# 1_Interface.net
KiCad netlist of a schematic drawn in Altium Designer
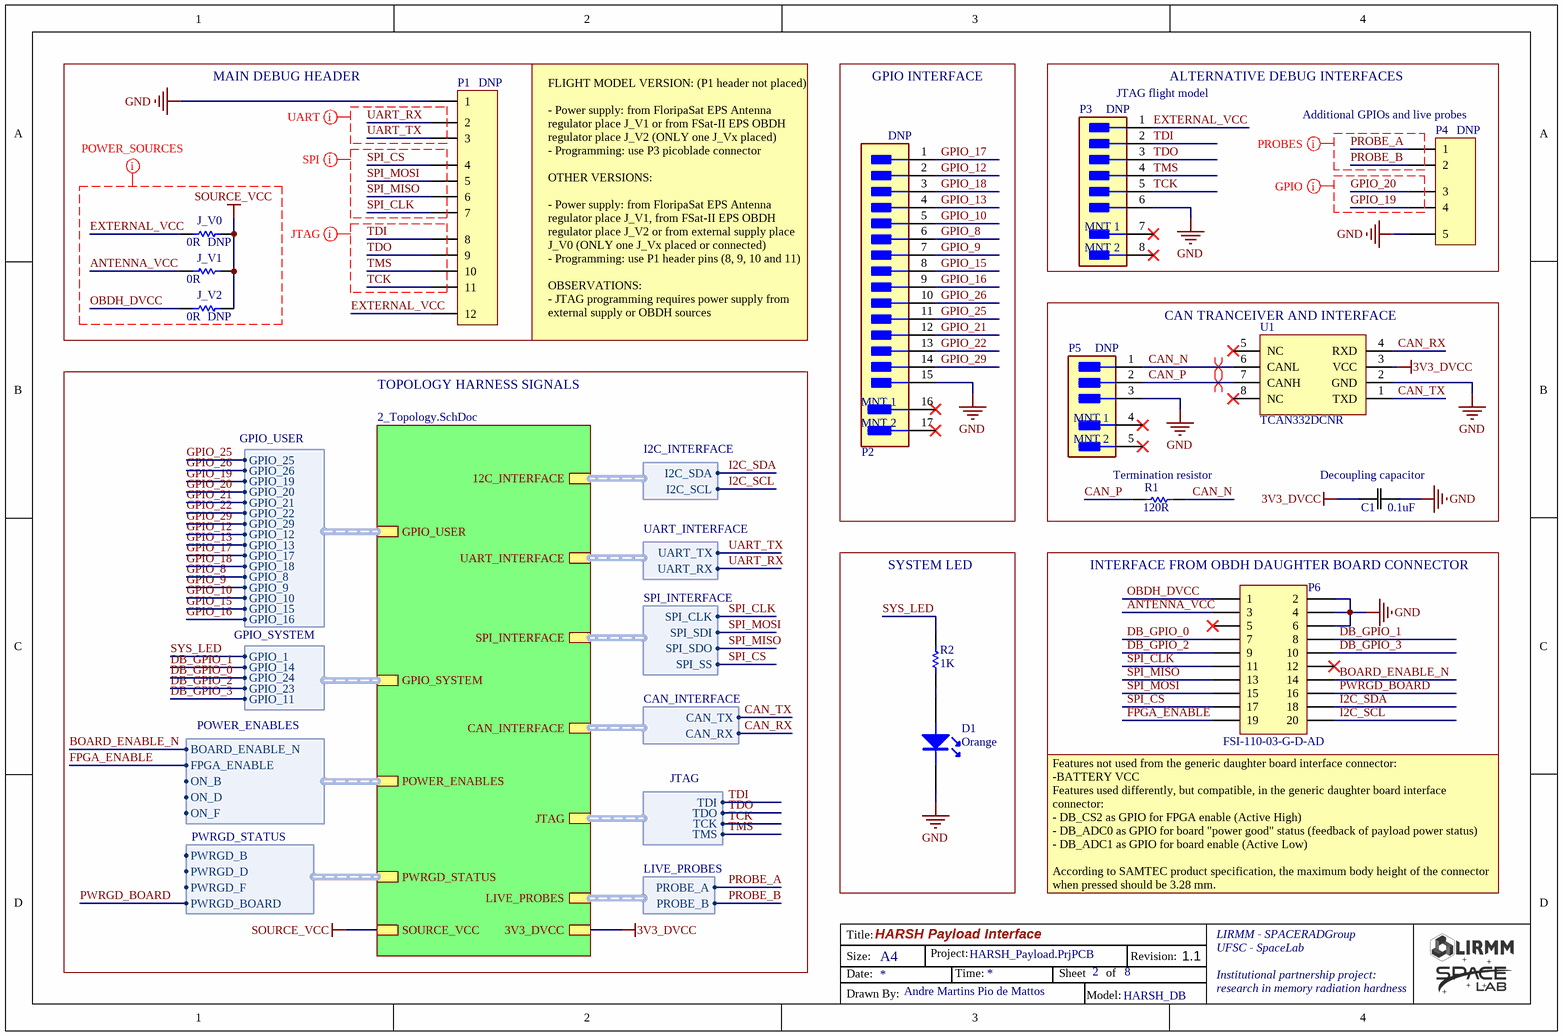
[diagram p0: 1_Interface.SchDoc]

(export (version "E")
  (design (tool "Eeschema 10.0.6"))
  (components
    (comp (ref "C1")
      (value "100nF/50V")
      (footprint "DONE_C0603")
      (description "CAP CER 100nF 50V 0603 10%")
      (fields
        (field (name "PARTNUMBER") "C0603C104K5RAC3121")
        (field (name "MANUFACTURER") "Yageo")
        (field (name "CAPACITANCE") "0.1uF")
      )
      (libsource (lib "HARSH_Payload_SchLib") (part "DONE_CAP_0.1uF_0603_X7R"))
    )
    (comp (ref "D1")
      (value "Orange")
      (footprint "DONE_D0603_ORANGE")
      (description "SMD Orange LED")
      (fields (field (name "PARTNUMBER") "HSML-C191-T0000"))
      (libsource (lib "HARSH_Payload_SchLib") (part "DONE_LED_ORANGE_0603"))
    )
    (comp (ref "J_V0")
      (value "0R")
      (footprint "DONE_R0603")
      (description "RES SMD 0 OHM JUMPER 1/10W 0603")
      (fields (field (name "PARTNUMBER") "RC0603JR-070RL"))
      (libsource (lib "HARSH_Payload_SchLib") (part "DONE_RES_0R_0603"))
    )
    (comp (ref "J_V1")
      (value "0R")
      (footprint "DONE_R0603")
      (description "RES SMD 0 OHM JUMPER 1/10W 0603")
      (fields (field (name "PARTNUMBER") "RC0603JR-070RL"))
      (libsource (lib "HARSH_Payload_SchLib") (part "DONE_RES_0R_0603"))
    )
    (comp (ref "J_V2")
      (value "0R")
      (footprint "DONE_R0603")
      (description "RES SMD 0 OHM JUMPER 1/10W 0603")
      (fields (field (name "PARTNUMBER") "RC0603JR-070RL"))
      (libsource (lib "HARSH_Payload_SchLib") (part "DONE_RES_0R_0603"))
    )
    (comp (ref "P1")
      (value "Header 12H")
      (footprint "DONE_H1X12_PADS")
      (description "Header, 12-Pin")
      (fields (field (name "PUBLISHER") "Altium Limited"))
      (libsource (lib "HARSH_Payload_SchLib") (part "DONE_H1X12_PADS"))
    )
    (comp (ref "P2")
      (value "53261-1571")
      (footprint "DONE_PICOBLADE_15H_HORIZONTAL")
      (description "Picoblade, 15 pos, Right-angle, 53261-1571")
      (libsource (lib "HARSH_Payload_SchLib") (part "DONE_PICOBLADE_15H"))
    )
    (comp (ref "P3")
      (value "53261-0671")
      (footprint "DONE_PICOBLADE_6H_HORIZONTAL")
      (description "Picoblade, 6 pos, Right-angle")
      (libsource (lib "HARSH_Payload_SchLib") (part "DONE_PICOBLADE_6H"))
    )
    (comp (ref "P4")
      (value "Header 5H")
      (footprint "DONE_H1X5_PADS")
      (description "Header, 5-Pin, Pads")
      (fields (field (name "PUBLISHER") "Altium Limited"))
      (libsource (lib "HARSH_Payload_SchLib") (part "DONE_H1X5_PADS"))
    )
    (comp (ref "P5")
      (value "53261-0371")
      (footprint "DONE_PICOBLADE_3H_HORIZONTAL")
      (description "Picoblade, 3 pos, Right-angle")
      (libsource (lib "HARSH_Payload_SchLib") (part "DONE_PICOBLADE_3H"))
    )
    (comp (ref "P6")
      (value "FSI-110-03-G-D-AD")
      (footprint "DONE_DB_INTERFACE")
      (description "CONN STACKING 20POS SMD GOLD")
      (fields
        (field (name "MANUFACTURER") "Samtec")
        (field (name "MANUFACTURER PART NUMBER") "FSI-110-03-G-D-AD")
      )
      (libsource (lib "HARSH_Payload_SchLib") (part "DONE_DB_INTERFACE"))
    )
    (comp (ref "R1")
      (value "120R")
      (footprint "DONE_R0603")
      (description "120R 1% 0603")
      (fields (field (name "RESISTANCE") "120R") (field (name "PARTNUMBER") "RC0603FR-07120RL"))
      (libsource (lib "HARSH_Payload_SchLib") (part "DONE_RES_120R_0603"))
    )
    (comp (ref "R2")
      (value "1K")
      (footprint "DONE_R0603")
      (description "RES SMD 1K OHM 1% 1/4W 0603")
      (fields
        (field (name "MANUFACTURER") "Rohm")
        (field (name "MANUFACTURER PART NUMBER") "ESR03EZPF1001")
        (field (name "RESISTANCE") "1K")
      )
      (libsource (lib "HARSH_Payload_SchLib") (part "DONE_RES_1K_0603"))
    )
    (comp (ref "U1")
      (value "TCAN332DCNR")
      (footprint "DONE_TSOT_23_8")
      (description "Tranceiver CAN, 8-pin SOT23")
      (fields (field (name "MANUFACTURER") "Texas Instruments") (field (name "PARTNUMBER") "TCAN332DCNR"))
      (libsource (lib "HARSH_Payload_SchLib") (part "DONE_TCAN332DCNR"))
    )
  )
  (nets
    (net (code "11") (name "/ANTENNA_VCC") (class "Default")
      (node (ref "J_V1") (pin "2") (pinfunction "2_2") (pintype "passive"))
      (node (ref "P6") (pin "3") (pinfunction "3_3") (pintype "passive"))
    )
    (net (code "12") (name "/BOARD_ENABLE_N") (class "Default")
      (node (ref "P6") (pin "14") (pinfunction "14_14") (pintype "passive"))
    )
    (net (code "13") (name "/CAN_N") (class "Default")
      (node (ref "P5") (pin "1") (pinfunction "1_1") (pintype "passive"))
      (node (ref "R1") (pin "1") (pinfunction "1_1") (pintype "passive"))
      (node (ref "U1") (pin "6") (pinfunction "CANL_6") (pintype "passive"))
    )
    (net (code "14") (name "/CAN_P") (class "Default")
      (node (ref "P5") (pin "2") (pinfunction "2_2") (pintype "passive"))
      (node (ref "R1") (pin "2") (pinfunction "2_2") (pintype "passive"))
      (node (ref "U1") (pin "7") (pinfunction "CANH_7") (pintype "passive"))
    )
    (net (code "15") (name "/CAN_RX") (class "Default")
      (node (ref "U1") (pin "4") (pinfunction "RXD_4") (pintype "passive"))
    )
    (net (code "16") (name "/CAN_TX") (class "Default")
      (node (ref "U1") (pin "1") (pinfunction "TXD_1") (pintype "passive"))
    )
    (net (code "17") (name "/DB_GPIO_0") (class "Default")
      (node (ref "P6") (pin "7") (pinfunction "7_7") (pintype "passive"))
    )
    (net (code "18") (name "/DB_GPIO_1") (class "Default")
      (node (ref "P6") (pin "8") (pinfunction "8_8") (pintype "passive"))
    )
    (net (code "19") (name "/DB_GPIO_2") (class "Default")
      (node (ref "P6") (pin "9") (pinfunction "9_9") (pintype "passive"))
    )
    (net (code "20") (name "/DB_GPIO_3") (class "Default")
      (node (ref "P6") (pin "10") (pinfunction "10_10") (pintype "passive"))
    )
    (net (code "21") (name "/EXTERNAL_VCC") (class "Default")
      (node (ref "J_V0") (pin "2") (pinfunction "2_2") (pintype "passive"))
      (node (ref "P1") (pin "12") (pinfunction "12_12") (pintype "passive"))
      (node (ref "P3") (pin "1") (pinfunction "1_1") (pintype "passive"))
    )
    (net (code "22") (name "/FPGA_ENABLE") (class "Default")
      (node (ref "P6") (pin "19") (pinfunction "19_19") (pintype "passive"))
    )
    (net (code "23") (name "/GPIO_8") (class "Default")
      (node (ref "P2") (pin "6") (pinfunction "6_6") (pintype "passive"))
    )
    (net (code "24") (name "/GPIO_9") (class "Default")
      (node (ref "P2") (pin "7") (pinfunction "7_7") (pintype "passive"))
    )
    (net (code "25") (name "/GPIO_10") (class "Default")
      (node (ref "P2") (pin "5") (pinfunction "5_5") (pintype "passive"))
    )
    (net (code "26") (name "/GPIO_12") (class "Default")
      (node (ref "P2") (pin "2") (pinfunction "2_2") (pintype "passive"))
    )
    (net (code "27") (name "/GPIO_13") (class "Default")
      (node (ref "P2") (pin "4") (pinfunction "4_4") (pintype "passive"))
    )
    (net (code "28") (name "/GPIO_15") (class "Default")
      (node (ref "P2") (pin "8") (pinfunction "8_8") (pintype "passive"))
    )
    (net (code "29") (name "/GPIO_16") (class "Default")
      (node (ref "P2") (pin "9") (pinfunction "9_9") (pintype "passive"))
    )
    (net (code "30") (name "/GPIO_17") (class "Default")
      (node (ref "P2") (pin "1") (pinfunction "1_1") (pintype "passive"))
    )
    (net (code "31") (name "/GPIO_18") (class "Default")
      (node (ref "P2") (pin "3") (pinfunction "3_3") (pintype "passive"))
    )
    (net (code "32") (name "/GPIO_19") (class "Default")
      (node (ref "P4") (pin "4") (pinfunction "4_4") (pintype "passive"))
    )
    (net (code "33") (name "/GPIO_20") (class "Default")
      (node (ref "P4") (pin "3") (pinfunction "3_3") (pintype "passive"))
    )
    (net (code "34") (name "/GPIO_21") (class "Default")
      (node (ref "P2") (pin "12") (pinfunction "12_12") (pintype "passive"))
    )
    (net (code "35") (name "/GPIO_22") (class "Default")
      (node (ref "P2") (pin "13") (pinfunction "13_13") (pintype "passive"))
    )
    (net (code "36") (name "/GPIO_25") (class "Default")
      (node (ref "P2") (pin "11") (pinfunction "11_11") (pintype "passive"))
    )
    (net (code "37") (name "/GPIO_26") (class "Default")
      (node (ref "P2") (pin "10") (pinfunction "10_10") (pintype "passive"))
    )
    (net (code "38") (name "/GPIO_29") (class "Default")
      (node (ref "P2") (pin "14") (pinfunction "14_14") (pintype "passive"))
    )
    (net (code "39") (name "/I2C_SCL") (class "Default")
      (node (ref "P6") (pin "20") (pinfunction "20_20") (pintype "passive"))
    )
    (net (code "40") (name "/I2C_SDA") (class "Default")
      (node (ref "P6") (pin "18") (pinfunction "18_18") (pintype "passive"))
    )
    (net (code "41") (name "/OBDH_DVCC") (class "Default")
      (node (ref "J_V2") (pin "2") (pinfunction "2_2") (pintype "passive"))
      (node (ref "P6") (pin "1") (pinfunction "1_1") (pintype "passive"))
    )
    (net (code "42") (name "/PROBE_A") (class "Default")
      (node (ref "P4") (pin "1") (pinfunction "1_1") (pintype "passive"))
    )
    (net (code "43") (name "/PROBE_B") (class "Default")
      (node (ref "P4") (pin "2") (pinfunction "2_2") (pintype "passive"))
    )
    (net (code "44") (name "/PWRGD_BOARD") (class "Default")
      (node (ref "P6") (pin "16") (pinfunction "16_16") (pintype "passive"))
    )
    (net (code "45") (name "/SPI_CLK") (class "Default")
      (node (ref "P1") (pin "7") (pinfunction "7_7") (pintype "passive"))
      (node (ref "P6") (pin "11") (pinfunction "11_11") (pintype "passive"))
    )
    (net (code "46") (name "/SPI_CS") (class "Default")
      (node (ref "P1") (pin "4") (pinfunction "4_4") (pintype "passive"))
      (node (ref "P6") (pin "17") (pinfunction "17_17") (pintype "passive"))
    )
    (net (code "47") (name "/SPI_MISO") (class "Default")
      (node (ref "P1") (pin "6") (pinfunction "6_6") (pintype "passive"))
      (node (ref "P6") (pin "13") (pinfunction "13_13") (pintype "passive"))
    )
    (net (code "48") (name "/SPI_MOSI") (class "Default")
      (node (ref "P1") (pin "5") (pinfunction "5_5") (pintype "passive"))
      (node (ref "P6") (pin "15") (pinfunction "15_15") (pintype "passive"))
    )
    (net (code "49") (name "/SYS_LED") (class "Default")
      (node (ref "R2") (pin "2") (pinfunction "2_2") (pintype "passive"))
    )
    (net (code "50") (name "/TCK") (class "Default")
      (node (ref "P1") (pin "11") (pinfunction "11_11") (pintype "passive"))
      (node (ref "P3") (pin "5") (pinfunction "5_5") (pintype "passive"))
    )
    (net (code "51") (name "/TDI") (class "Default")
      (node (ref "P1") (pin "8") (pinfunction "8_8") (pintype "passive"))
      (node (ref "P3") (pin "2") (pinfunction "2_2") (pintype "passive"))
    )
    (net (code "52") (name "/TDO") (class "Default")
      (node (ref "P1") (pin "9") (pinfunction "9_9") (pintype "passive"))
      (node (ref "P3") (pin "3") (pinfunction "3_3") (pintype "passive"))
    )
    (net (code "53") (name "/TMS") (class "Default")
      (node (ref "P1") (pin "10") (pinfunction "10_10") (pintype "passive"))
      (node (ref "P3") (pin "4") (pinfunction "4_4") (pintype "passive"))
    )
    (net (code "54") (name "/UART_RX") (class "Default")
      (node (ref "P1") (pin "2") (pinfunction "2_2") (pintype "passive"))
    )
    (net (code "55") (name "/UART_TX") (class "Default")
      (node (ref "P1") (pin "3") (pinfunction "3_3") (pintype "passive"))
    )
    (net (code "66") (name "3V3_DVCC") (class "Default")
      (node (ref "C1") (pin "1") (pinfunction "1_1") (pintype "passive"))
      (node (ref "U1") (pin "3") (pinfunction "VCC_3") (pintype "passive"))
    )
    (net (code "67") (name "GND") (class "Default")
      (node (ref "C1") (pin "2") (pinfunction "2_2") (pintype "passive"))
      (node (ref "D1") (pin "2") (pinfunction "K_2") (pintype "passive"))
      (node (ref "P1") (pin "1") (pinfunction "1_1") (pintype "passive"))
      (node (ref "P2") (pin "15") (pinfunction "15_15") (pintype "passive"))
      (node (ref "P3") (pin "6") (pinfunction "6_6") (pintype "passive"))
      (node (ref "P4") (pin "5") (pinfunction "5_5") (pintype "passive"))
      (node (ref "P5") (pin "3") (pinfunction "3_3") (pintype "passive"))
      (node (ref "P6") (pin "2") (pinfunction "2_2") (pintype "passive"))
      (node (ref "P6") (pin "4") (pinfunction "4_4") (pintype "passive"))
      (node (ref "P6") (pin "6") (pinfunction "6_6") (pintype "passive"))
      (node (ref "U1") (pin "2") (pinfunction "GND_2") (pintype "passive"))
    )
    (net (code "68") (name "Net-(D1-A)") (class "Default")
      (node (ref "D1") (pin "1") (pinfunction "A_1") (pintype "passive"))
      (node (ref "R2") (pin "1") (pinfunction "1_1") (pintype "passive"))
    )
    (net (code "69") (name "SOURCE_VCC") (class "Default")
      (node (ref "J_V0") (pin "1") (pinfunction "1_1") (pintype "passive"))
      (node (ref "J_V1") (pin "1") (pinfunction "1_1") (pintype "passive"))
      (node (ref "J_V2") (pin "1") (pinfunction "1_1") (pintype "passive"))
    )
    (net (code "70") (name "unconnected-(P2-MNT_1-Pad16)") (class "Default")
      (node (ref "P2") (pin "16") (pinfunction "MNT_1_16") (pintype "passive+no_connect"))
    )
    (net (code "71") (name "unconnected-(P2-MNT_2-Pad17)") (class "Default")
      (node (ref "P2") (pin "17") (pinfunction "MNT_2_17") (pintype "passive+no_connect"))
    )
    (net (code "72") (name "unconnected-(P3-MNT_1-Pad7)") (class "Default")
      (node (ref "P3") (pin "7") (pinfunction "MNT_1_7") (pintype "passive+no_connect"))
    )
    (net (code "73") (name "unconnected-(P3-MNT_2-Pad8)") (class "Default")
      (node (ref "P3") (pin "8") (pinfunction "MNT_2_8") (pintype "passive+no_connect"))
    )
    (net (code "74") (name "unconnected-(P5-MNT_1-Pad4)") (class "Default")
      (node (ref "P5") (pin "4") (pinfunction "MNT_1_4") (pintype "passive+no_connect"))
    )
    (net (code "75") (name "unconnected-(P5-MNT_2-Pad5)") (class "Default")
      (node (ref "P5") (pin "5") (pinfunction "MNT_2_5") (pintype "passive+no_connect"))
    )
    (net (code "76") (name "unconnected-(P6-Pad5)") (class "Default")
      (node (ref "P6") (pin "5") (pinfunction "5_5") (pintype "passive+no_connect"))
    )
    (net (code "77") (name "unconnected-(P6-Pad12)") (class "Default")
      (node (ref "P6") (pin "12") (pinfunction "12_12") (pintype "passive+no_connect"))
    )
    (net (code "78") (name "unconnected-(U1-NC-Pad5)") (class "Default")
      (node (ref "U1") (pin "5") (pinfunction "NC_5") (pintype "passive+no_connect"))
    )
    (net (code "79") (name "unconnected-(U1-NC-Pad8)") (class "Default")
      (node (ref "U1") (pin "8") (pinfunction "NC_8") (pintype "passive+no_connect"))
    )
  )
)
